# Power_Distribution_-_Solar_Sense_Telemet.net
KiCad netlist of a schematic drawn in Altium Designer
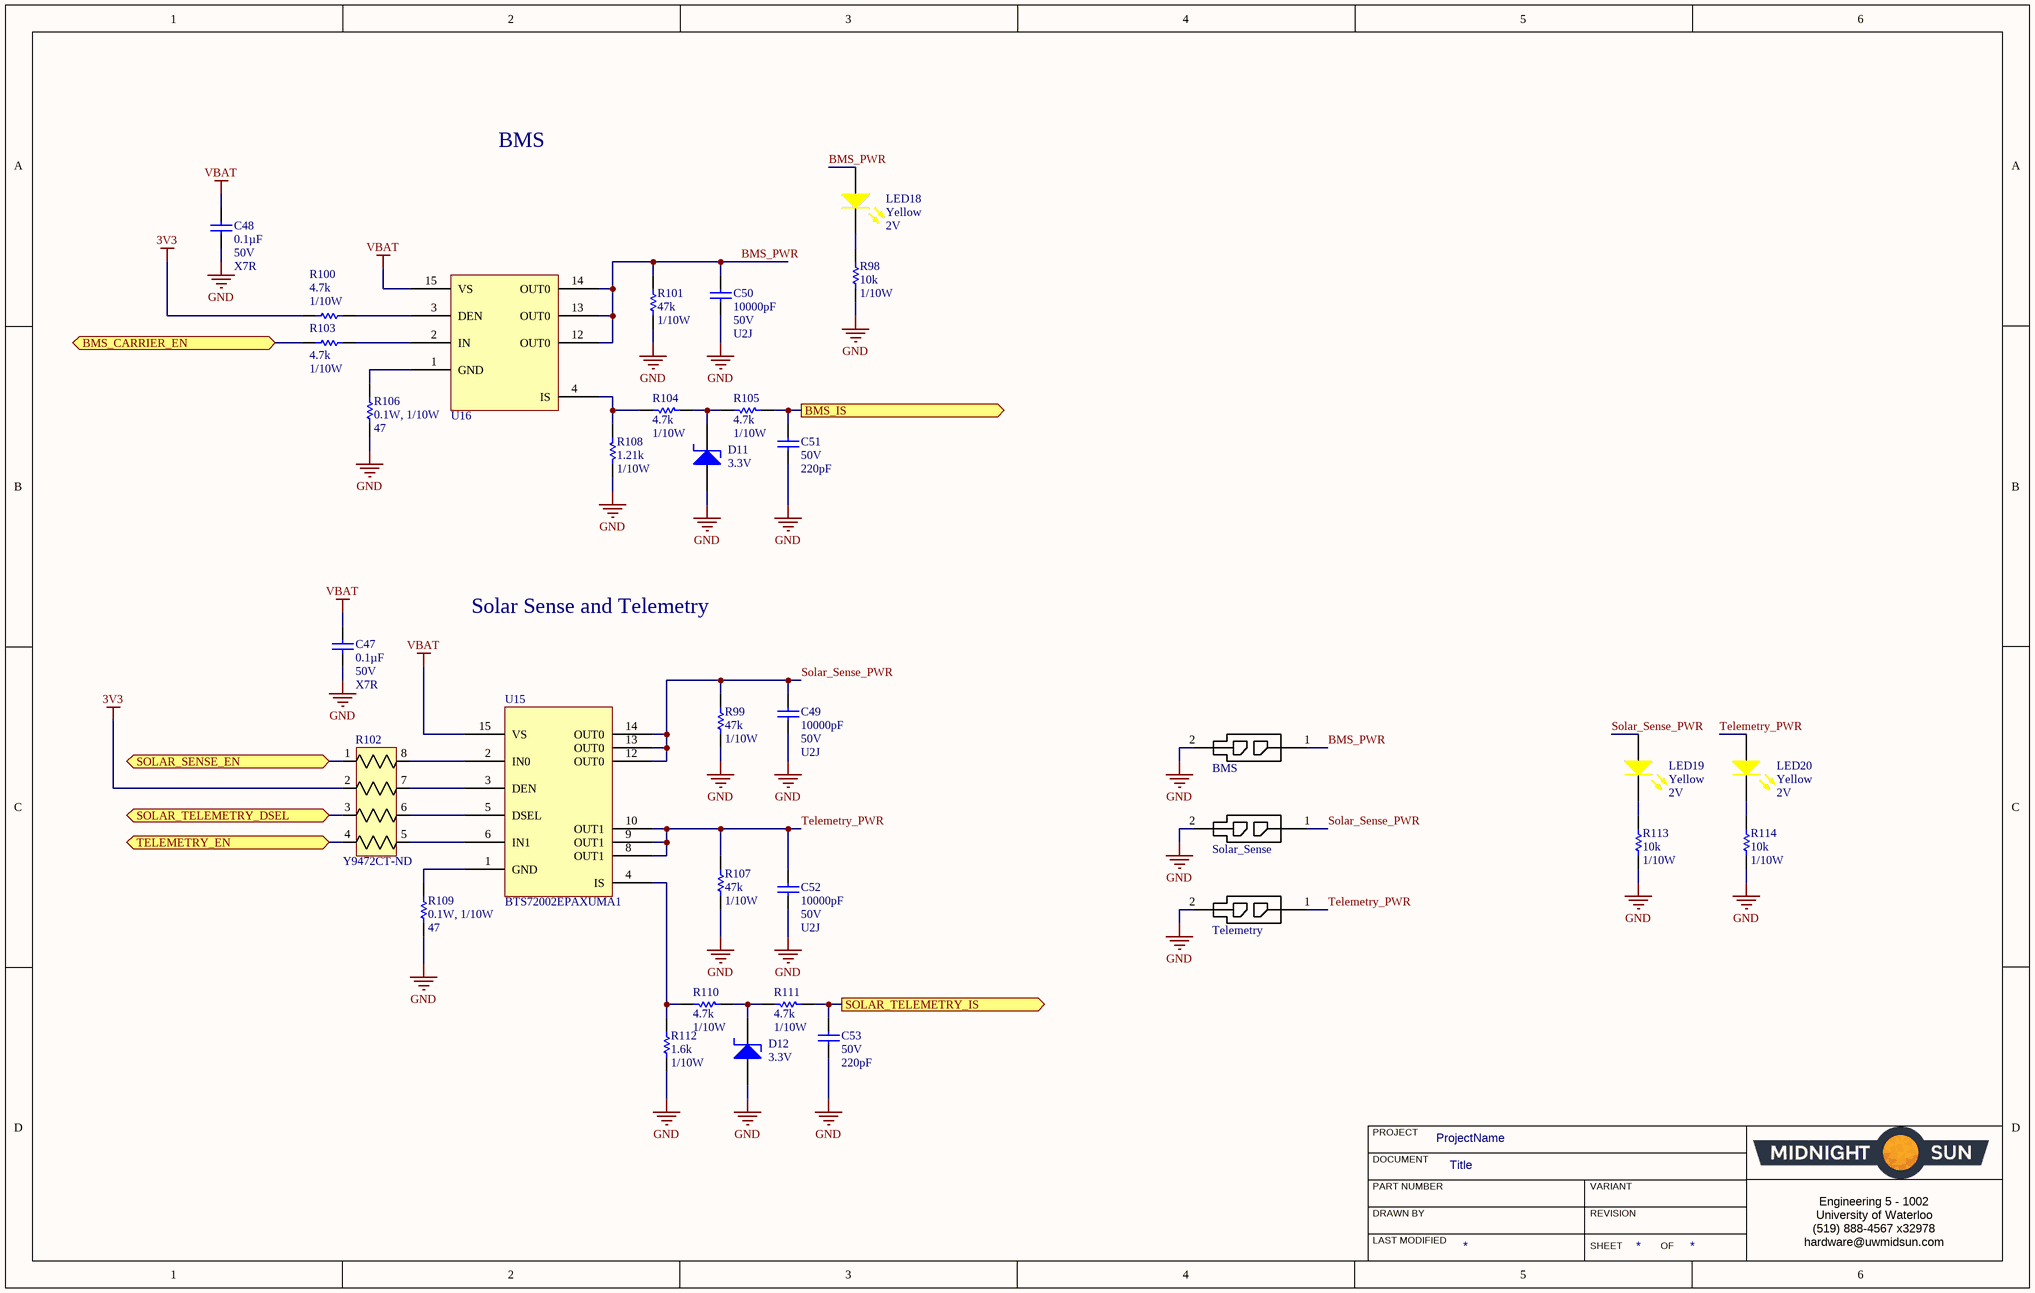
[diagram p0: Power Distribution - Solar Sense, Telemetry, and BMS.SchDoc]

(export (version "E")
  (design (tool "Eeschema 10.0.6"))
  (components
    (comp (ref "BMS")
      (value "CONN 2POS MICRO-FIT 3mm")
      (footprint "CONN, 2POS MICRO-FIT")
      (description "Connector Header Through Hole 2 position")
      (fields (field (name "MANUFACTURER") "Molex") (field (name "MANUFACTURER PART NUMBER") "43045-0227"))
      (libsource (lib "Schematic Diagrams") (part "CONN 2POS MICRO-FIT 3mm"))
    )
    (comp (ref "C47")
      (value "CAP CER 0.1UF 50V 10% X7R 0603")
      (footprint "CAP, 0603")
      (description "0.10µF ±10% 50V Ceramic Capacitor X7R 0603 (1608 Metric)")
      (fields
        (field (name "TOLERANCE") "±10%")
        (field (name "CAPACITANCE") "0.1µF")
        (field (name "VOLTAGE") "50V")
        (field (name "TEMPERATURE COEFFICIENT") "X7R")
      )
      (libsource (lib "Schematic Diagrams") (part "CAP CER 0.1UF 50V 10% X7R 0603"))
    )
    (comp (ref "C48")
      (value "CAP CER 0.1UF 50V 10% X7R 0603")
      (footprint "CAP, 0603")
      (description "0.10µF ±10% 50V Ceramic Capacitor X7R 0603 (1608 Metric)")
      (fields
        (field (name "TOLERANCE") "±10%")
        (field (name "CAPACITANCE") "0.1µF")
        (field (name "VOLTAGE") "50V")
        (field (name "TEMPERATURE COEFFICIENT") "X7R")
      )
      (libsource (lib "Schematic Diagrams") (part "CAP CER 0.1UF 50V 10% X7R 0603"))
    )
    (comp (ref "C49")
      (value "CAP CER 10nF 50V 5% X7R 0603")
      (footprint "CAP, 0603")
      (description "10000pF ±5% 50V Ceramic Capacitor U2J 0603 (1608 Metric)")
      (fields
        (field (name "TOLERANCE") "±5%")
        (field (name "CAPACITANCE") "10000pF")
        (field (name "VOLTAGE") "50V")
        (field (name "TEMPERATURE COEFFICIENT") "U2J")
      )
      (libsource (lib "Schematic Diagrams") (part "CAP CER 10nF 50V 5% X7R 0603"))
    )
    (comp (ref "C50")
      (value "CAP CER 10nF 50V 5% X7R 0603")
      (footprint "CAP, 0603")
      (description "10000pF ±5% 50V Ceramic Capacitor U2J 0603 (1608 Metric)")
      (fields
        (field (name "TOLERANCE") "±5%")
        (field (name "CAPACITANCE") "10000pF")
        (field (name "VOLTAGE") "50V")
        (field (name "TEMPERATURE COEFFICIENT") "U2J")
      )
      (libsource (lib "Schematic Diagrams") (part "CAP CER 10nF 50V 5% X7R 0603"))
    )
    (comp (ref "C51")
      (value "CAP CER 220PF 50V C0G/NP0 0603")
      (footprint "CAP, 0603")
      (description "220pF ±5% 50V Ceramic Capacitor C0G, NP0 0603 (1608 Metric)")
      (fields
        (field (name "MANUFACTURER") "KEMET")
        (field (name "TOLERANCE") "5%")
        (field (name "VOLTAGE RATING") "50V")
        (field (name "CAPACITANCE") "220pF")
      )
      (libsource (lib "Schematic Diagrams") (part "CAP CER 220PF 50V C0G/NP0 0603"))
    )
    (comp (ref "C52")
      (value "CAP CER 10nF 50V 5% X7R 0603")
      (footprint "CAP, 0603")
      (description "10000pF ±5% 50V Ceramic Capacitor U2J 0603 (1608 Metric)")
      (fields
        (field (name "TOLERANCE") "±5%")
        (field (name "CAPACITANCE") "10000pF")
        (field (name "VOLTAGE") "50V")
        (field (name "TEMPERATURE COEFFICIENT") "U2J")
      )
      (libsource (lib "Schematic Diagrams") (part "CAP CER 10nF 50V 5% X7R 0603"))
    )
    (comp (ref "C53")
      (value "CAP CER 220PF 50V C0G/NP0 0603")
      (footprint "CAP, 0603")
      (description "220pF ±5% 50V Ceramic Capacitor C0G, NP0 0603 (1608 Metric)")
      (fields
        (field (name "MANUFACTURER") "KEMET")
        (field (name "TOLERANCE") "5%")
        (field (name "VOLTAGE RATING") "50V")
        (field (name "CAPACITANCE") "220pF")
      )
      (libsource (lib "Schematic Diagrams") (part "CAP CER 220PF 50V C0G/NP0 0603"))
    )
    (comp (ref "D11")
      (value "DIODE ZENER 3.3V 200MW SOD323")
      (footprint "sod-323")
      (description "Zener Diode 3.3V 200mW ±5% Surface Mount SOD-323")
      (fields (field (name "VOLTAGE") "3.3V"))
      (libsource (lib "Schematic Diagrams") (part "DIODE ZENER 3.3V 200MW SOD323"))
    )
    (comp (ref "D12")
      (value "DIODE ZENER 3.3V 200MW SOD323")
      (footprint "sod-323")
      (description "Zener Diode 3.3V 200mW ±5% Surface Mount SOD-323")
      (fields (field (name "VOLTAGE") "3.3V"))
      (libsource (lib "Schematic Diagrams") (part "DIODE ZENER 3.3V 200MW SOD323"))
    )
    (comp (ref "LED18")
      (value "LED YELLOW CLEAR 2.1V 0603")
      (footprint "LED_0603")
      (description "Yellow 590nm LED Indication - Discrete 2V 0603 (1608 Metric)")
      (fields
        (field (name "MANUFACTURER") "Wurth Electronics Inc.")
        (field (name "MANUFACTURER PART NUMBER") "150060YS75000")
        (field (name "COLOR") "Yellow")
        (field (name "VOLTAGE - FORWARD (VF) (TYP)") "2V")
      )
      (libsource (lib "Schematic Diagrams") (part "LED YELLOW CLEAR 2.1V 0603"))
    )
    (comp (ref "LED19")
      (value "LED YELLOW CLEAR 2.1V 0603")
      (footprint "LED_0603")
      (description "Yellow 590nm LED Indication - Discrete 2V 0603 (1608 Metric)")
      (fields
        (field (name "MANUFACTURER") "Wurth Electronics Inc.")
        (field (name "MANUFACTURER PART NUMBER") "150060YS75000")
        (field (name "COLOR") "Yellow")
        (field (name "VOLTAGE - FORWARD (VF) (TYP)") "2V")
      )
      (libsource (lib "Schematic Diagrams") (part "LED YELLOW CLEAR 2.1V 0603"))
    )
    (comp (ref "LED20")
      (value "LED YELLOW CLEAR 2.1V 0603")
      (footprint "LED_0603")
      (description "Yellow 590nm LED Indication - Discrete 2V 0603 (1608 Metric)")
      (fields
        (field (name "MANUFACTURER") "Wurth Electronics Inc.")
        (field (name "MANUFACTURER PART NUMBER") "150060YS75000")
        (field (name "COLOR") "Yellow")
        (field (name "VOLTAGE - FORWARD (VF) (TYP)") "2V")
      )
      (libsource (lib "Schematic Diagrams") (part "LED YELLOW CLEAR 2.1V 0603"))
    )
    (comp (ref "R98")
      (value "RES 10K OHM 1% 1/10W 0603")
      (footprint "RES, 0603")
      (description "RES SMD 10K OHM 1% 1/10W 0603")
      (fields
        (field (name "TOLERANCE") "±1%")
        (field (name "RESISTANCE") "10k")
        (field (name "POWER") "1/10W")
      )
      (libsource (lib "Schematic Diagrams") (part "RES 10K OHM 1% 1/10W 0603"))
    )
    (comp (ref "R99")
      (value "RES 47K OHM 1% 1/10W 0603")
      (footprint "RES, 0603")
      (description "47 kOhms ±1% 0.1W, 1/10W Chip Resistor 0603 (1608 Metric) Automotive AEC-Q200 Thick Film")
      (fields
        (field (name "MANUFACTURER") "Panasonic")
        (field (name "MANUFACTURER PART NUMBER") "ERJ3EKF4702V")
        (field (name "RESISTANCE") "47k")
        (field (name "POWER RATING") "1/10W")
      )
      (libsource (lib "Schematic Diagrams") (part "RES 47K OHM 1% 1/10W 0603"))
    )
    (comp (ref "R100")
      (value "RES 4.7K OHM 1% 1/10W 0603")
      (footprint "RES, 0603")
      (description "4.7k Ohm ±1% 0.1W, 1/10W Chip Resistor 0603 (1608 Metric) Moisture Resistant Thick Film")
      (fields
        (field (name "TOLERANCE") "±1%")
        (field (name "RESISTANCE (OHMS)") "4.7k")
        (field (name "POWER (WATTS)") "1/10W")
      )
      (libsource (lib "Schematic Diagrams") (part "RES 4.7K OHM 1% 1/10W 0603"))
    )
    (comp (ref "R101")
      (value "RES 47K OHM 1% 1/10W 0603")
      (footprint "RES, 0603")
      (description "47 kOhms ±1% 0.1W, 1/10W Chip Resistor 0603 (1608 Metric) Automotive AEC-Q200 Thick Film")
      (fields
        (field (name "MANUFACTURER") "Panasonic")
        (field (name "MANUFACTURER PART NUMBER") "ERJ3EKF4702V")
        (field (name "RESISTANCE") "47k")
        (field (name "POWER RATING") "1/10W")
      )
      (libsource (lib "Schematic Diagrams") (part "RES 47K OHM 1% 1/10W 0603"))
    )
    (comp (ref "R102")
      (value "RES ARRAY 4 RES 4.7K OHM 1206")
      (footprint "RES ARRAY 4RES 1206")
      (fields (field (name "TOLERANCE") "±5%") (field (name "SUPPLIER PART NUMBER 1") "Y9472CT-ND"))
      (libsource (lib "Schematic Diagrams") (part "RES ARRAY 4 RES 4.7K OHM 1206"))
    )
    (comp (ref "R103")
      (value "RES 4.7K OHM 1% 1/10W 0603")
      (footprint "RES, 0603")
      (description "4.7k Ohm ±1% 0.1W, 1/10W Chip Resistor 0603 (1608 Metric) Moisture Resistant Thick Film")
      (fields
        (field (name "TOLERANCE") "±1%")
        (field (name "RESISTANCE (OHMS)") "4.7k")
        (field (name "POWER (WATTS)") "1/10W")
      )
      (libsource (lib "Schematic Diagrams") (part "RES 4.7K OHM 1% 1/10W 0603"))
    )
    (comp (ref "R104")
      (value "RES 4.7K OHM 1% 1/10W 0603")
      (footprint "RES, 0603")
      (description "4.7k Ohm ±1% 0.1W, 1/10W Chip Resistor 0603 (1608 Metric) Moisture Resistant Thick Film")
      (fields
        (field (name "TOLERANCE") "±1%")
        (field (name "RESISTANCE (OHMS)") "4.7k")
        (field (name "POWER (WATTS)") "1/10W")
      )
      (libsource (lib "Schematic Diagrams") (part "RES 4.7K OHM 1% 1/10W 0603"))
    )
    (comp (ref "R105")
      (value "RES 4.7K OHM 1% 1/10W 0603")
      (footprint "RES, 0603")
      (description "4.7k Ohm ±1% 0.1W, 1/10W Chip Resistor 0603 (1608 Metric) Moisture Resistant Thick Film")
      (fields
        (field (name "TOLERANCE") "±1%")
        (field (name "RESISTANCE (OHMS)") "4.7k")
        (field (name "POWER (WATTS)") "1/10W")
      )
      (libsource (lib "Schematic Diagrams") (part "RES 4.7K OHM 1% 1/10W 0603"))
    )
    (comp (ref "R106")
      (value "RES SMD 47 OHM 1% 1/10W 0603")
      (footprint "RES, 0603")
      (fields
        (field (name "TOLERANCE") "±1%")
        (field (name "POWER (WATTS)") "0.1W, 1/10W")
        (field (name "VALUES") "47")
      )
      (libsource (lib "Schematic Diagrams") (part "RES SMD 47 OHM 1% 1/10W 0603"))
    )
    (comp (ref "R107")
      (value "RES 47K OHM 1% 1/10W 0603")
      (footprint "RES, 0603")
      (description "47 kOhms ±1% 0.1W, 1/10W Chip Resistor 0603 (1608 Metric) Automotive AEC-Q200 Thick Film")
      (fields
        (field (name "MANUFACTURER") "Panasonic")
        (field (name "MANUFACTURER PART NUMBER") "ERJ3EKF4702V")
        (field (name "RESISTANCE") "47k")
        (field (name "POWER RATING") "1/10W")
      )
      (libsource (lib "Schematic Diagrams") (part "RES 47K OHM 1% 1/10W 0603"))
    )
    (comp (ref "R108")
      (value "RES 1.21K OHM 1% 1/10W 0603")
      (footprint "RES, 0603")
      (description "1.21k Ohm ±1% 0.1W, 1/10W Chip Resistor 0603 (1608 Metric) Moisture Resistant Thick Film")
      (fields
        (field (name "TOLERANCE") "±1%")
        (field (name "RESISTANCE") "1.21k")
        (field (name "POWER") "1/10W")
      )
      (libsource (lib "Schematic Diagrams") (part "RES 1.21K OHM 1% 1/10W 0603"))
    )
    (comp (ref "R109")
      (value "RES SMD 47 OHM 1% 1/10W 0603")
      (footprint "RES, 0603")
      (fields
        (field (name "TOLERANCE") "±1%")
        (field (name "POWER (WATTS)") "0.1W, 1/10W")
        (field (name "VALUES") "47")
      )
      (libsource (lib "Schematic Diagrams") (part "RES SMD 47 OHM 1% 1/10W 0603"))
    )
    (comp (ref "R110")
      (value "RES 4.7K OHM 1% 1/10W 0603")
      (footprint "RES, 0603")
      (description "4.7k Ohm ±1% 0.1W, 1/10W Chip Resistor 0603 (1608 Metric) Moisture Resistant Thick Film")
      (fields
        (field (name "TOLERANCE") "±1%")
        (field (name "RESISTANCE (OHMS)") "4.7k")
        (field (name "POWER (WATTS)") "1/10W")
      )
      (libsource (lib "Schematic Diagrams") (part "RES 4.7K OHM 1% 1/10W 0603"))
    )
    (comp (ref "R111")
      (value "RES 4.7K OHM 1% 1/10W 0603")
      (footprint "RES, 0603")
      (description "4.7k Ohm ±1% 0.1W, 1/10W Chip Resistor 0603 (1608 Metric) Moisture Resistant Thick Film")
      (fields
        (field (name "TOLERANCE") "±1%")
        (field (name "RESISTANCE (OHMS)") "4.7k")
        (field (name "POWER (WATTS)") "1/10W")
      )
      (libsource (lib "Schematic Diagrams") (part "RES 4.7K OHM 1% 1/10W 0603"))
    )
    (comp (ref "R112")
      (value "RES 1.6K OHM 1% 1/10W 0603")
      (footprint "RES, 0603")
      (description "1.6 kOhms ±1% 0.1W, 1/10W Chip Resistor 0603 (1608 Metric) Moisture Resistant Thick Film")
      (fields
        (field (name "MANUFACTURER") "Yageo")
        (field (name "MANUFACTURER PART NUMBER") "RC0603FR-071K6L")
        (field (name "RESISTANCE") "1.6k")
        (field (name "POWER RATING") "1/10W")
      )
      (libsource (lib "Schematic Diagrams") (part "RES 1.6K OHM 1% 1/10W 0603"))
    )
    (comp (ref "R113")
      (value "RES 10K OHM 1% 1/10W 0603")
      (footprint "RES, 0603")
      (description "RES SMD 10K OHM 1% 1/10W 0603")
      (fields
        (field (name "TOLERANCE") "±1%")
        (field (name "RESISTANCE") "10k")
        (field (name "POWER") "1/10W")
      )
      (libsource (lib "Schematic Diagrams") (part "RES 10K OHM 1% 1/10W 0603"))
    )
    (comp (ref "R114")
      (value "RES 10K OHM 1% 1/10W 0603")
      (footprint "RES, 0603")
      (description "RES SMD 10K OHM 1% 1/10W 0603")
      (fields
        (field (name "TOLERANCE") "±1%")
        (field (name "RESISTANCE") "10k")
        (field (name "POWER") "1/10W")
      )
      (libsource (lib "Schematic Diagrams") (part "RES 10K OHM 1% 1/10W 0603"))
    )
    (comp (ref "Solar_Sense")
      (value "CONN 2POS MICRO-FIT 3mm")
      (footprint "CONN, 2POS MICRO-FIT")
      (description "Connector Header Through Hole 2 position")
      (fields (field (name "MANUFACTURER") "Molex") (field (name "MANUFACTURER PART NUMBER") "43045-0227"))
      (libsource (lib "Schematic Diagrams") (part "CONN 2POS MICRO-FIT 3mm"))
    )
    (comp (ref "Telemetry")
      (value "CONN 2POS MICRO-FIT 3mm")
      (footprint "CONN, 2POS MICRO-FIT")
      (description "Connector Header Through Hole 2 position")
      (fields (field (name "MANUFACTURER") "Molex") (field (name "MANUFACTURER PART NUMBER") "43045-0227"))
      (libsource (lib "Schematic Diagrams") (part "CONN 2POS MICRO-FIT 3mm"))
    )
    (comp (ref "U15")
      (value "IC LOAD SWITCH BTS7200-2EPA PG-TSDSO-14_1")
      (footprint "IC LOAD SWITCH PG-TSDSO-14-22")
      (description "Power Switch/Driver 1:1 N-Channel 1.2A PG-TSDSO-14-22")
      (fields
        (field (name "MANUFACTURER") "Infineon")
        (field (name "MANUFACTURER PART NUMBER") "BTS72002EPAXUMA1")
      )
      (libsource (lib "Schematic Diagrams") (part "IC LOAD SWITCH BTS7200-2EPA PG-TSDSO-14_1"))
    )
    (comp (ref "U16")
      (value "IC LOAD SWITCH BTS70401EPA PG-TSDSO-14-22")
      (footprint "IC LOAD SWITCH PG-TSDSO-14-22")
      (description "Power Switch/Driver 1:1 N-Channel 4.5A PG-TSDSO-14-22")
      (fields
        (field (name "MANUFACTURER") "Infineon")
        (field (name "MANUFACTURER PART NUMBER") "BTS70401EPAXUMA1")
      )
      (libsource (lib "Schematic Diagrams") (part "IC LOAD SWITCH BTS70401EPA PG-TSDSO-14-22"))
    )
  )
  (nets
    (net (code "1") (name "/BMS_CARRIER_EN") (class "Default")
      (node (ref "R103") (pin "1") (pinfunction "1_1") (pintype "passive"))
    )
    (net (code "2") (name "/BMS_IS") (class "Default")
      (node (ref "C51") (pin "1") (pinfunction "1_1") (pintype "passive"))
      (node (ref "R105") (pin "1") (pinfunction "1_1") (pintype "passive"))
    )
    (net (code "3") (name "/BMS_PWR") (class "Default")
      (node (ref "BMS") (pin "1") (pinfunction "1_1") (pintype "passive"))
      (node (ref "C50") (pin "1") (pinfunction "1_1") (pintype "passive"))
      (node (ref "LED18") (pin "1") (pinfunction "A_1") (pintype "passive"))
      (node (ref "R101") (pin "1") (pinfunction "1_1") (pintype "passive"))
      (node (ref "U16") (pin "12") (pinfunction "OUT0_12") (pintype "passive"))
      (node (ref "U16") (pin "13") (pinfunction "OUT0_13") (pintype "passive"))
      (node (ref "U16") (pin "14") (pinfunction "OUT0_14") (pintype "passive"))
    )
    (net (code "4") (name "/SOLAR_SENSE_EN") (class "Default")
      (node (ref "R102") (pin "1") (pinfunction "1_1") (pintype "passive"))
    )
    (net (code "5") (name "/SOLAR_TELEMETRY_DSEL") (class "Default")
      (node (ref "R102") (pin "3") (pinfunction "3_3") (pintype "passive"))
    )
    (net (code "6") (name "/SOLAR_TELEMETRY_IS") (class "Default")
      (node (ref "C53") (pin "1") (pinfunction "1_1") (pintype "passive"))
      (node (ref "R111") (pin "1") (pinfunction "1_1") (pintype "passive"))
    )
    (net (code "7") (name "/Solar_Sense_PWR") (class "Default")
      (node (ref "C49") (pin "1") (pinfunction "1_1") (pintype "passive"))
      (node (ref "LED19") (pin "1") (pinfunction "A_1") (pintype "passive"))
      (node (ref "R99") (pin "1") (pinfunction "1_1") (pintype "passive"))
      (node (ref "Solar_Sense") (pin "1") (pinfunction "1_1") (pintype "passive"))
      (node (ref "U15") (pin "12") (pinfunction "OUT0_12") (pintype "passive"))
      (node (ref "U15") (pin "13") (pinfunction "OUT0_13") (pintype "passive"))
      (node (ref "U15") (pin "14") (pinfunction "OUT0_14") (pintype "passive"))
    )
    (net (code "8") (name "/TELEMETRY_EN") (class "Default")
      (node (ref "R102") (pin "4") (pinfunction "4_4") (pintype "passive"))
    )
    (net (code "9") (name "/Telemetry_PWR") (class "Default")
      (node (ref "C52") (pin "1") (pinfunction "1_1") (pintype "passive"))
      (node (ref "LED20") (pin "1") (pinfunction "A_1") (pintype "passive"))
      (node (ref "R107") (pin "1") (pinfunction "1_1") (pintype "passive"))
      (node (ref "Telemetry") (pin "1") (pinfunction "1_1") (pintype "passive"))
      (node (ref "U15") (pin "10") (pinfunction "OUT1_10") (pintype "passive"))
      (node (ref "U15") (pin "8") (pinfunction "OUT1_8") (pintype "passive"))
      (node (ref "U15") (pin "9") (pinfunction "OUT1_9") (pintype "passive"))
    )
    (net (code "10") (name "3V3") (class "Default")
      (node (ref "R100") (pin "1") (pinfunction "1_1") (pintype "passive"))
      (node (ref "R102") (pin "2") (pinfunction "2_2") (pintype "passive"))
    )
    (net (code "11") (name "GND") (class "Default")
      (node (ref "BMS") (pin "2") (pinfunction "2_2") (pintype "passive"))
      (node (ref "C47") (pin "2") (pinfunction "2_2") (pintype "passive"))
      (node (ref "C48") (pin "2") (pinfunction "2_2") (pintype "passive"))
      (node (ref "C49") (pin "2") (pinfunction "2_2") (pintype "passive"))
      (node (ref "C50") (pin "2") (pinfunction "2_2") (pintype "passive"))
      (node (ref "C51") (pin "2") (pinfunction "2_2") (pintype "passive"))
      (node (ref "C52") (pin "2") (pinfunction "2_2") (pintype "passive"))
      (node (ref "C53") (pin "2") (pinfunction "2_2") (pintype "passive"))
      (node (ref "D11") (pin "1") (pinfunction "A_1") (pintype "passive"))
      (node (ref "D12") (pin "1") (pinfunction "A_1") (pintype "passive"))
      (node (ref "R101") (pin "2") (pinfunction "2_2") (pintype "passive"))
      (node (ref "R106") (pin "2") (pinfunction "2_2") (pintype "passive"))
      (node (ref "R107") (pin "2") (pinfunction "2_2") (pintype "passive"))
      (node (ref "R108") (pin "2") (pinfunction "2_2") (pintype "passive"))
      (node (ref "R109") (pin "2") (pinfunction "2_2") (pintype "passive"))
      (node (ref "R112") (pin "2") (pinfunction "2_2") (pintype "passive"))
      (node (ref "R113") (pin "2") (pinfunction "2_2") (pintype "passive"))
      (node (ref "R114") (pin "2") (pinfunction "2_2") (pintype "passive"))
      (node (ref "R98") (pin "2") (pinfunction "2_2") (pintype "passive"))
      (node (ref "R99") (pin "2") (pinfunction "2_2") (pintype "passive"))
      (node (ref "Solar_Sense") (pin "2") (pinfunction "2_2") (pintype "passive"))
      (node (ref "Telemetry") (pin "2") (pinfunction "2_2") (pintype "passive"))
    )
    (net (code "12") (name "Net-(D11-K)") (class "Default")
      (node (ref "D11") (pin "2") (pinfunction "K_2") (pintype "passive"))
      (node (ref "R104") (pin "1") (pinfunction "1_1") (pintype "passive"))
      (node (ref "R105") (pin "2") (pinfunction "2_2") (pintype "passive"))
    )
    (net (code "13") (name "Net-(D12-K)") (class "Default")
      (node (ref "D12") (pin "2") (pinfunction "K_2") (pintype "passive"))
      (node (ref "R110") (pin "1") (pinfunction "1_1") (pintype "passive"))
      (node (ref "R111") (pin "2") (pinfunction "2_2") (pintype "passive"))
    )
    (net (code "14") (name "Net-(LED18-K)") (class "Default")
      (node (ref "LED18") (pin "2") (pinfunction "K_2") (pintype "passive"))
      (node (ref "R98") (pin "1") (pinfunction "1_1") (pintype "passive"))
    )
    (net (code "15") (name "Net-(LED19-K)") (class "Default")
      (node (ref "LED19") (pin "2") (pinfunction "K_2") (pintype "passive"))
      (node (ref "R113") (pin "1") (pinfunction "1_1") (pintype "passive"))
    )
    (net (code "16") (name "Net-(LED20-K)") (class "Default")
      (node (ref "LED20") (pin "2") (pinfunction "K_2") (pintype "passive"))
      (node (ref "R114") (pin "1") (pinfunction "1_1") (pintype "passive"))
    )
    (net (code "17") (name "Net-(U15-DEN)") (class "Default")
      (node (ref "R102") (pin "7") (pinfunction "7_7") (pintype "passive"))
      (node (ref "U15") (pin "3") (pinfunction "DEN_3") (pintype "passive"))
    )
    (net (code "18") (name "Net-(U15-DSEL)") (class "Default")
      (node (ref "R102") (pin "6") (pinfunction "6_6") (pintype "passive"))
      (node (ref "U15") (pin "5") (pinfunction "DSEL_5") (pintype "passive"))
    )
    (net (code "19") (name "Net-(U15-GND)") (class "Default")
      (node (ref "R109") (pin "1") (pinfunction "1_1") (pintype "passive"))
      (node (ref "U15") (pin "1") (pinfunction "GND_1") (pintype "passive"))
    )
    (net (code "20") (name "Net-(U15-IN0)") (class "Default")
      (node (ref "R102") (pin "8") (pinfunction "8_8") (pintype "passive"))
      (node (ref "U15") (pin "2") (pinfunction "IN0_2") (pintype "passive"))
    )
    (net (code "21") (name "Net-(U15-IN1)") (class "Default")
      (node (ref "R102") (pin "5") (pinfunction "5_5") (pintype "passive"))
      (node (ref "U15") (pin "6") (pinfunction "IN1_6") (pintype "passive"))
    )
    (net (code "22") (name "Net-(U15-IS)") (class "Default")
      (node (ref "R110") (pin "2") (pinfunction "2_2") (pintype "passive"))
      (node (ref "R112") (pin "1") (pinfunction "1_1") (pintype "passive"))
      (node (ref "U15") (pin "4") (pinfunction "IS_4") (pintype "passive"))
    )
    (net (code "23") (name "Net-(U16-DEN)") (class "Default")
      (node (ref "R100") (pin "2") (pinfunction "2_2") (pintype "passive"))
      (node (ref "U16") (pin "3") (pinfunction "DEN_3") (pintype "passive"))
    )
    (net (code "24") (name "Net-(U16-GND)") (class "Default")
      (node (ref "R106") (pin "1") (pinfunction "1_1") (pintype "passive"))
      (node (ref "U16") (pin "1") (pinfunction "GND_1") (pintype "passive"))
    )
    (net (code "25") (name "Net-(U16-IN)") (class "Default")
      (node (ref "R103") (pin "2") (pinfunction "2_2") (pintype "passive"))
      (node (ref "U16") (pin "2") (pinfunction "IN_2") (pintype "passive"))
    )
    (net (code "26") (name "Net-(U16-IS)") (class "Default")
      (node (ref "R104") (pin "2") (pinfunction "2_2") (pintype "passive"))
      (node (ref "R108") (pin "1") (pinfunction "1_1") (pintype "passive"))
      (node (ref "U16") (pin "4") (pinfunction "IS_4") (pintype "passive"))
    )
    (net (code "27") (name "VBAT") (class "Default")
      (node (ref "C47") (pin "1") (pinfunction "1_1") (pintype "passive"))
      (node (ref "C48") (pin "1") (pinfunction "1_1") (pintype "passive"))
      (node (ref "U15") (pin "15") (pinfunction "VS_15") (pintype "passive"))
      (node (ref "U16") (pin "15") (pinfunction "VS_15") (pintype "passive"))
    )
  )
)
